# Somador_DC.net
KiCad netlist of a schematic drawn in Altium Designer
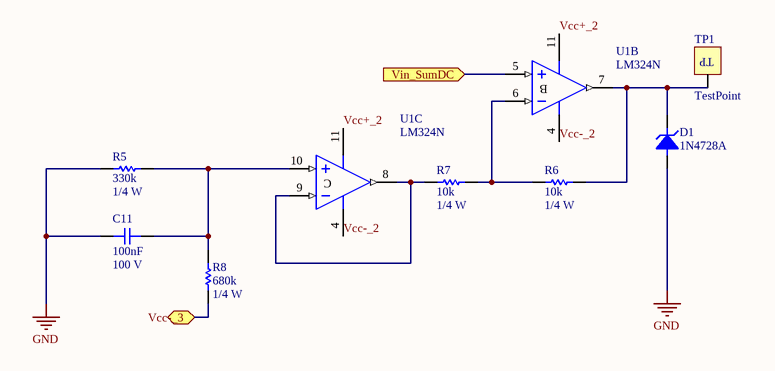
[diagram p0: Somador_DC.SchDoc]

(export (version "E")
  (design (tool "Eeschema 10.0.6"))
  (components
    (comp (ref "C11")
      (value "100nF")
      (footprint "0805C")
      (description "Capacitor")
      (fields (field (name "VOLTAGE") "100 V") (field (name "PUBLISHER") "Altium Limited"))
      (libsource (lib "GPDSE") (part "Capacitor"))
    )
    (comp (ref "D1")
      (value "1N4728A")
      (footprint "DO-41-Glass")
      (description "Zener Diode")
      (libsource (lib "GPDSE") (part "1N4728A"))
    )
    (comp (ref "R5")
      (value "330k")
      (footprint "0805R")
      (description "Resistor")
      (fields
        (field (name "TOLERANCE") "5%")
        (field (name "POWER") "1/4 W")
        (field (name "PUBLISHER") "Altium Limited")
      )
      (libsource (lib "GPDSE") (part "Resistor"))
    )
    (comp (ref "R6")
      (value "10k")
      (footprint "0805R")
      (description "Resistor")
      (fields
        (field (name "TOLERANCE") "5%")
        (field (name "POWER") "1/4 W")
        (field (name "PUBLISHER") "Altium Limited")
      )
      (libsource (lib "GPDSE") (part "Resistor"))
    )
    (comp (ref "R7")
      (value "10k")
      (footprint "0805R")
      (description "Resistor")
      (fields
        (field (name "TOLERANCE") "5%")
        (field (name "POWER") "1/4 W")
        (field (name "PUBLISHER") "Altium Limited")
      )
      (libsource (lib "GPDSE") (part "Resistor"))
    )
    (comp (ref "R8")
      (value "680k")
      (footprint "0805R")
      (description "Resistor")
      (fields
        (field (name "TOLERANCE") "5%")
        (field (name "POWER") "1/4 W")
        (field (name "PUBLISHER") "Altium Limited")
      )
      (libsource (lib "GPDSE") (part "Resistor"))
    )
    (comp (ref "TP1")
      (value "TestPoint")
      (footprint "TEST_POINT_PTH")
      (description "Test Point")
      (libsource (lib "GPDSE") (part "TestPoint"))
    )
    (comp (ref "U1")
      (value "LM324N")
      (footprint "N014")
      (description "Quadruple Operational Amplifier")
      (fields (field (name "PUBLISHER") "Altium Limited"))
      (libsource (lib "TI Operational Amplifier") (part "LM324N"))
    )
  )
  (nets
    (net (code "1") (name "/Vcc+_2") (class "Default")
      (node (ref "U1") (pin "11") (pinfunction "V-_11") (pintype "power_in"))
    )
    (net (code "2") (name "/Vcc-_2") (class "Default")
      (node (ref "U1") (pin "4") (pinfunction "V+_4") (pintype "power_in"))
    )
    (net (code "3") (name "/Vcc-_3") (class "Default")
      (node (ref "R8") (pin "1") (pinfunction "1_1") (pintype "passive"))
    )
    (net (code "4") (name "/Vin_SumDC") (class "Default")
      (node (ref "U1") (pin "5") (pinfunction "IN+_5") (pintype "input"))
    )
    (net (code "5") (name "GND") (class "Default")
      (node (ref "C11") (pin "2") (pinfunction "2_2") (pintype "passive"))
      (node (ref "D1") (pin "A") (pinfunction "A_A") (pintype "passive"))
      (node (ref "R5") (pin "2") (pinfunction "2_2") (pintype "passive"))
    )
    (net (code "6") (name "Net-(TP1-TP)") (class "Default")
      (node (ref "D1") (pin "K") (pinfunction "K_K") (pintype "passive"))
      (node (ref "R6") (pin "2") (pinfunction "2_2") (pintype "passive"))
      (node (ref "TP1") (pin "1") (pinfunction "TP_1") (pintype "passive"))
      (node (ref "U1") (pin "7") (pinfunction "OUT_7") (pintype "output"))
    )
    (net (code "7") (name "Net-(U1B-IN-)") (class "Default")
      (node (ref "R6") (pin "1") (pinfunction "1_1") (pintype "passive"))
      (node (ref "R7") (pin "2") (pinfunction "2_2") (pintype "passive"))
      (node (ref "U1") (pin "6") (pinfunction "IN-_6") (pintype "input"))
    )
    (net (code "8") (name "Net-(U1C-IN+)") (class "Default")
      (node (ref "C11") (pin "1") (pinfunction "1_1") (pintype "passive"))
      (node (ref "R5") (pin "1") (pinfunction "1_1") (pintype "passive"))
      (node (ref "R8") (pin "2") (pinfunction "2_2") (pintype "passive"))
      (node (ref "U1") (pin "10") (pinfunction "IN+_10") (pintype "input"))
    )
    (net (code "9") (name "Net-(U1C-IN-)") (class "Default")
      (node (ref "R7") (pin "1") (pinfunction "1_1") (pintype "passive"))
      (node (ref "U1") (pin "8") (pinfunction "OUT_8") (pintype "output"))
      (node (ref "U1") (pin "9") (pinfunction "IN-_9") (pintype "input"))
    )
  )
)
